# module_board.net
KiCad netlist of a schematic drawn in Altium Designer
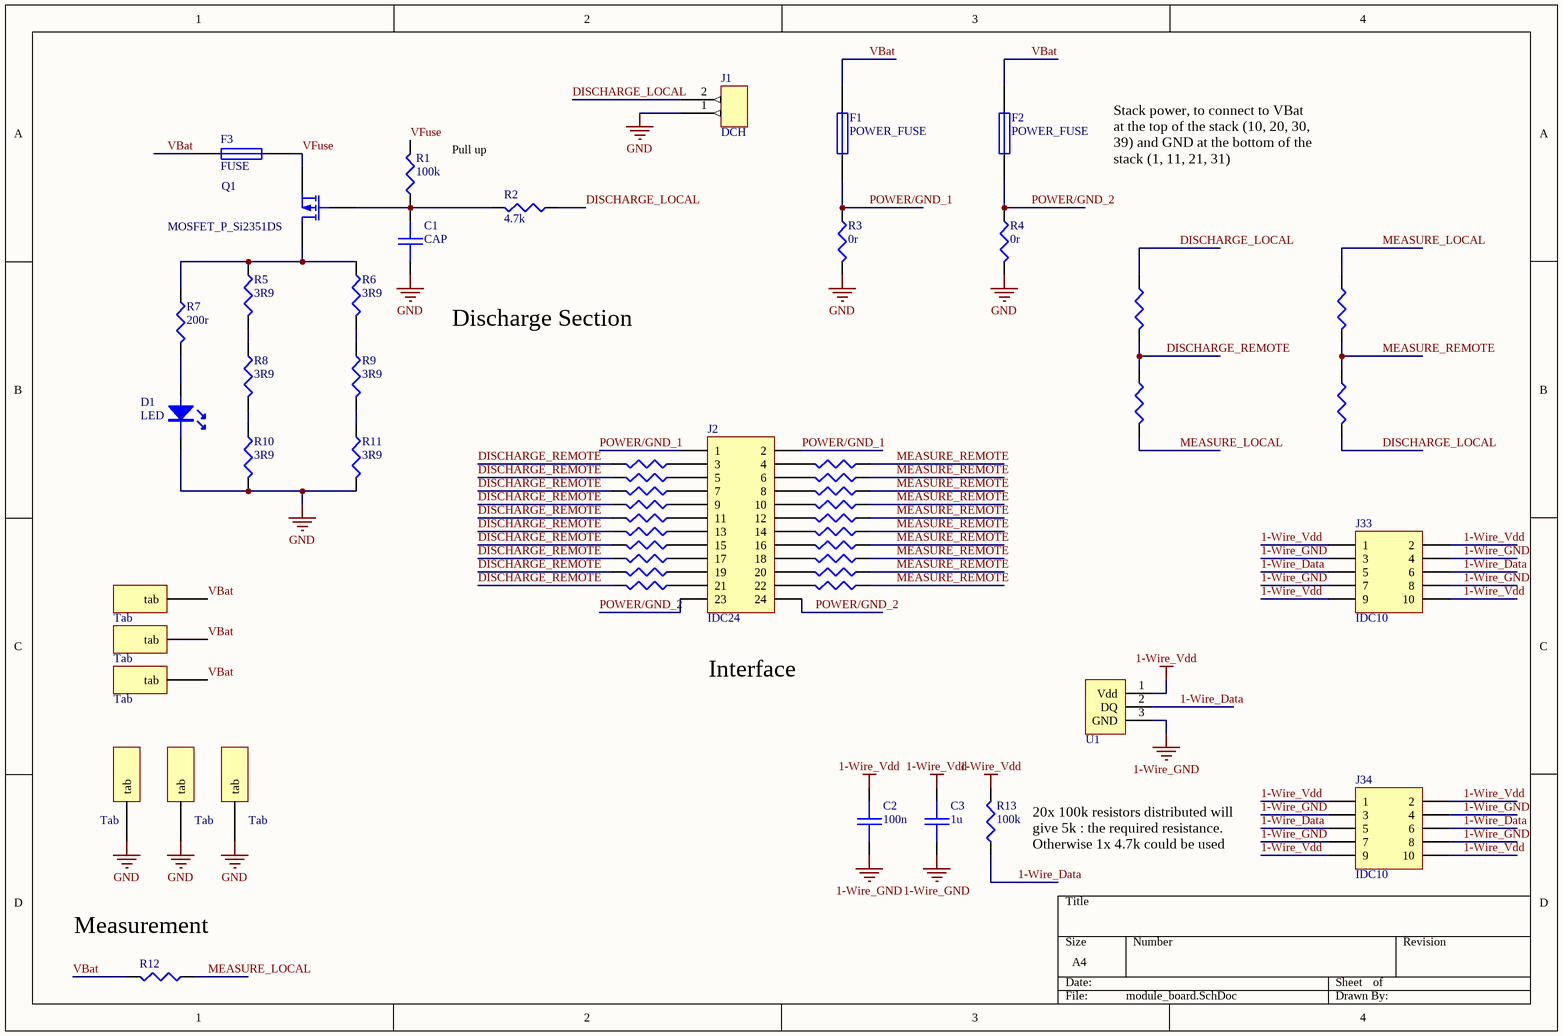
[diagram p0: module_board.SchDoc]

(export (version "E")
  (design (tool "Eeschema 10.0.6"))
  (components
    (comp (ref "C1")
      (value "CAP")
      (footprint "0603")
      (description "Capacitor")
      (libsource (lib "RCLDQ") (part "CAP"))
    )
    (comp (ref "C2")
      (value "100n")
      (footprint "0603")
      (description "Capacitor")
      (libsource (lib "RCLDQ") (part "CAP"))
    )
    (comp (ref "C3")
      (value "1u")
      (footprint "0805")
      (description "Capacitor")
      (libsource (lib "RCLDQ") (part "CAP"))
    )
    (comp (ref "D1") (value "LED") (footprint "0805LED") (libsource (lib "RCLDQ") (part "LED")))
    (comp (ref "F1")
      (value "POWER_FUSE")
      (footprint "LITTELFUSE-154")
      (description "Fuse")
      (libsource (lib "Miscellaneous") (part "FUSE"))
    )
    (comp (ref "F2")
      (value "POWER_FUSE")
      (footprint "LITTELFUSE-154")
      (description "Fuse")
      (libsource (lib "Miscellaneous") (part "FUSE"))
    )
    (comp (ref "F3")
      (value "FUSE")
      (footprint "LITTELFUSE-154")
      (description "Fuse")
      (libsource (lib "Miscellaneous") (part "FUSE"))
    )
    (comp (ref "J1") (value "DCH") (footprint "IDC2") (libsource (lib "Connectors") (part "CON2")))
    (comp (ref "J2")
      (value "IDC24")
      (footprint "IDC24")
      (description "Connector")
      (libsource (lib "Connectors") (part "IDC24"))
    )
    (comp (ref "J11") (value "Tab") (footprint "tab_connect") (libsource (lib "") (part "tab_connection_1")))
    (comp (ref "J20") (value "Tab") (footprint "tab_connect") (libsource (lib "") (part "tab_connection_1")))
    (comp (ref "J27") (value "Tab") (footprint "tab_connect") (libsource (lib "") (part "tab_connection_1")))
    (comp (ref "J30") (value "Tab") (footprint "tab_connect") (libsource (lib "BMS") (part "tab_connection")))
    (comp (ref "J31") (value "Tab") (footprint "tab_connect") (libsource (lib "BMS") (part "tab_connection")))
    (comp (ref "J32") (value "Tab") (footprint "tab_connect") (libsource (lib "BMS") (part "tab_connection")))
    (comp (ref "J33")
      (value "IDC10")
      (footprint "IDC10")
      (description "Connector")
      (libsource (lib "Connectors") (part "IDC10"))
    )
    (comp (ref "J34")
      (value "IDC10")
      (footprint "IDC10")
      (description "Connector")
      (libsource (lib "Connectors") (part "IDC10"))
    )
    (comp (ref "Q1")
      (value "MOSFET_P_Si2351DS")
      (footprint "SOT23-3")
      (description "Si2351DS P-Channel MOSFET")
      (fields (field (name "PUBLISHER") "Altium Limited"))
      (libsource (lib "RCLDQ") (part "MOSFET_P_Si2351DS"))
    )
    (comp (ref "R1")
      (value "100k")
      (footprint "0603")
      (description "Resistor")
      (libsource (lib "RCLDQ") (part "RES1"))
    )
    (comp (ref "R2")
      (value "4.7k")
      (footprint "1206")
      (description "Resistor")
      (libsource (lib "RCLDQ") (part "RES1"))
    )
    (comp (ref "R3")
      (value "~")
      (footprint "1206")
      (description "Resistor")
      (fields (field (name "RESISTANCE") "0r"))
      (libsource (lib "RCLDQ") (part "RES1"))
    )
    (comp (ref "R4")
      (value "~")
      (footprint "1206")
      (description "Resistor")
      (fields (field (name "RESISTANCE") "0r"))
      (libsource (lib "RCLDQ") (part "RES1"))
    )
    (comp (ref "R5")
      (value "3R9")
      (footprint "2512")
      (description "Resistor")
      (libsource (lib "RCLDQ") (part "RES1"))
    )
    (comp (ref "R6")
      (value "3R9")
      (footprint "2512")
      (description "Resistor")
      (libsource (lib "RCLDQ") (part "RES1"))
    )
    (comp (ref "R7")
      (value "200r")
      (footprint "0603")
      (description "Resistor")
      (libsource (lib "RCLDQ") (part "RES1"))
    )
    (comp (ref "R8")
      (value "3R9")
      (footprint "2512")
      (description "Resistor")
      (libsource (lib "RCLDQ") (part "RES1"))
    )
    (comp (ref "R9")
      (value "3R9")
      (footprint "2512")
      (description "Resistor")
      (libsource (lib "RCLDQ") (part "RES1"))
    )
    (comp (ref "R10")
      (value "3R9")
      (footprint "2512")
      (description "Resistor")
      (libsource (lib "RCLDQ") (part "RES1"))
    )
    (comp (ref "R11")
      (value "3R9")
      (footprint "2512")
      (description "Resistor")
      (libsource (lib "RCLDQ") (part "RES1"))
    )
    (comp (ref "R12")
      (value "4.7k")
      (footprint "1206")
      (description "Resistor")
      (libsource (lib "RCLDQ") (part "RES1"))
    )
    (comp (ref "R13")
      (value "100k")
      (footprint "0603")
      (description "Resistor")
      (libsource (lib "RCLDQ") (part "RES1"))
    )
    (comp (ref "R14")
      (value "0k")
      (footprint "0603")
      (description "Resistor")
      (libsource (lib "RCLDQ") (part "RES1"))
    )
    (comp (ref "R15")
      (value "0k")
      (footprint "0603")
      (description "Resistor")
      (libsource (lib "RCLDQ") (part "RES1"))
    )
    (comp (ref "R16")
      (value "0k")
      (footprint "0603")
      (description "Resistor")
      (libsource (lib "RCLDQ") (part "RES1"))
    )
    (comp (ref "R17")
      (value "0k")
      (footprint "0603")
      (description "Resistor")
      (libsource (lib "RCLDQ") (part "RES1"))
    )
    (comp (ref "R18")
      (value "0k")
      (footprint "0603")
      (description "Resistor")
      (libsource (lib "RCLDQ") (part "RES1"))
    )
    (comp (ref "R19")
      (value "0k")
      (footprint "0603")
      (description "Resistor")
      (libsource (lib "RCLDQ") (part "RES1"))
    )
    (comp (ref "R20")
      (value "0k")
      (footprint "0603")
      (description "Resistor")
      (libsource (lib "RCLDQ") (part "RES1"))
    )
    (comp (ref "R21")
      (value "0k")
      (footprint "0603")
      (description "Resistor")
      (libsource (lib "RCLDQ") (part "RES1"))
    )
    (comp (ref "R22")
      (value "0k")
      (footprint "0603")
      (description "Resistor")
      (libsource (lib "RCLDQ") (part "RES1"))
    )
    (comp (ref "R23")
      (value "0k")
      (footprint "0603")
      (description "Resistor")
      (libsource (lib "RCLDQ") (part "RES1"))
    )
    (comp (ref "R24")
      (value "0k")
      (footprint "0603")
      (description "Resistor")
      (libsource (lib "RCLDQ") (part "RES1"))
    )
    (comp (ref "R25")
      (value "0k")
      (footprint "0603")
      (description "Resistor")
      (libsource (lib "RCLDQ") (part "RES1"))
    )
    (comp (ref "R26")
      (value "0k")
      (footprint "0603")
      (description "Resistor")
      (libsource (lib "RCLDQ") (part "RES1"))
    )
    (comp (ref "R27")
      (value "0k")
      (footprint "0603")
      (description "Resistor")
      (libsource (lib "RCLDQ") (part "RES1"))
    )
    (comp (ref "R28")
      (value "0k")
      (footprint "0603")
      (description "Resistor")
      (libsource (lib "RCLDQ") (part "RES1"))
    )
    (comp (ref "R29")
      (value "0k")
      (footprint "0603")
      (description "Resistor")
      (libsource (lib "RCLDQ") (part "RES1"))
    )
    (comp (ref "R30")
      (value "0k")
      (footprint "0603")
      (description "Resistor")
      (libsource (lib "RCLDQ") (part "RES1"))
    )
    (comp (ref "R31")
      (value "0k")
      (footprint "0603")
      (description "Resistor")
      (libsource (lib "RCLDQ") (part "RES1"))
    )
    (comp (ref "R32")
      (value "0k")
      (footprint "0603")
      (description "Resistor")
      (libsource (lib "RCLDQ") (part "RES1"))
    )
    (comp (ref "R33")
      (value "0k")
      (footprint "0603")
      (description "Resistor")
      (libsource (lib "RCLDQ") (part "RES1"))
    )
    (comp (ref "R34")
      (value "0k")
      (footprint "0603")
      (description "Resistor")
      (libsource (lib "RCLDQ") (part "RES1"))
    )
    (comp (ref "R35")
      (value "0k")
      (footprint "0603")
      (description "Resistor")
      (libsource (lib "RCLDQ") (part "RES1"))
    )
    (comp (ref "R36")
      (value "0k")
      (footprint "0603")
      (description "Resistor")
      (libsource (lib "RCLDQ") (part "RES1"))
    )
    (comp (ref "R37")
      (value "0k")
      (footprint "0603")
      (description "Resistor")
      (libsource (lib "RCLDQ") (part "RES1"))
    )
    (comp (ref "U1")
      (value "DS18B20")
      (footprint "TO-92")
      (description "DS18B20 1-Wire Temperature sensor")
      (libsource (lib "BMS") (part "DS18B20"))
    )
  )
  (nets
    (net (code "1") (name "/1-Wire_Data") (class "Default")
      (node (ref "J33") (pin "5") (pinfunction "5_5") (pintype "passive"))
      (node (ref "J33") (pin "6") (pinfunction "6_6") (pintype "passive"))
      (node (ref "J34") (pin "5") (pinfunction "5_5") (pintype "passive"))
      (node (ref "J34") (pin "6") (pinfunction "6_6") (pintype "passive"))
      (node (ref "R13") (pin "1") (pinfunction "1_1") (pintype "passive"))
      (node (ref "U1") (pin "2") (pinfunction "DQ_2") (pintype "passive"))
    )
    (net (code "2") (name "/DISCHARGE_LOCAL") (class "Default")
      (node (ref "J1") (pin "2") (pinfunction "2_2") (pintype "output"))
      (node (ref "R2") (pin "1") (pinfunction "1_1") (pintype "passive"))
      (node (ref "R34") (pin "1") (pinfunction "1_1") (pintype "passive"))
      (node (ref "R37") (pin "2") (pinfunction "2_2") (pintype "passive"))
    )
    (net (code "3") (name "/DISCHARGE_REMOTE") (class "Default")
      (node (ref "R14") (pin "2") (pinfunction "2_2") (pintype "passive"))
      (node (ref "R16") (pin "2") (pinfunction "2_2") (pintype "passive"))
      (node (ref "R18") (pin "2") (pinfunction "2_2") (pintype "passive"))
      (node (ref "R20") (pin "2") (pinfunction "2_2") (pintype "passive"))
      (node (ref "R22") (pin "2") (pinfunction "2_2") (pintype "passive"))
      (node (ref "R24") (pin "2") (pinfunction "2_2") (pintype "passive"))
      (node (ref "R26") (pin "2") (pinfunction "2_2") (pintype "passive"))
      (node (ref "R28") (pin "2") (pinfunction "2_2") (pintype "passive"))
      (node (ref "R30") (pin "2") (pinfunction "2_2") (pintype "passive"))
      (node (ref "R32") (pin "2") (pinfunction "2_2") (pintype "passive"))
      (node (ref "R34") (pin "2") (pinfunction "2_2") (pintype "passive"))
      (node (ref "R36") (pin "1") (pinfunction "1_1") (pintype "passive"))
    )
    (net (code "4") (name "/MEASURE_LOCAL") (class "Default")
      (node (ref "R12") (pin "1") (pinfunction "1_1") (pintype "passive"))
      (node (ref "R35") (pin "1") (pinfunction "1_1") (pintype "passive"))
      (node (ref "R36") (pin "2") (pinfunction "2_2") (pintype "passive"))
    )
    (net (code "5") (name "/MEASURE_REMOTE") (class "Default")
      (node (ref "R15") (pin "1") (pinfunction "1_1") (pintype "passive"))
      (node (ref "R17") (pin "1") (pinfunction "1_1") (pintype "passive"))
      (node (ref "R19") (pin "1") (pinfunction "1_1") (pintype "passive"))
      (node (ref "R21") (pin "1") (pinfunction "1_1") (pintype "passive"))
      (node (ref "R23") (pin "1") (pinfunction "1_1") (pintype "passive"))
      (node (ref "R25") (pin "1") (pinfunction "1_1") (pintype "passive"))
      (node (ref "R27") (pin "1") (pinfunction "1_1") (pintype "passive"))
      (node (ref "R29") (pin "1") (pinfunction "1_1") (pintype "passive"))
      (node (ref "R31") (pin "1") (pinfunction "1_1") (pintype "passive"))
      (node (ref "R33") (pin "1") (pinfunction "1_1") (pintype "passive"))
      (node (ref "R35") (pin "2") (pinfunction "2_2") (pintype "passive"))
      (node (ref "R37") (pin "1") (pinfunction "1_1") (pintype "passive"))
    )
    (net (code "6") (name "/POWER{slash}GND_1") (class "Default")
      (node (ref "F1") (pin "1") (pinfunction "1_1") (pintype "passive"))
      (node (ref "J2") (pin "1") (pinfunction "1_1") (pintype "passive"))
      (node (ref "J2") (pin "2") (pinfunction "2_2") (pintype "passive"))
      (node (ref "R3") (pin "1") (pinfunction "1_1") (pintype "passive"))
    )
    (net (code "7") (name "/POWER{slash}GND_2") (class "Default")
      (node (ref "F2") (pin "1") (pinfunction "1_1") (pintype "passive"))
      (node (ref "J2") (pin "23") (pinfunction "23_23") (pintype "passive"))
      (node (ref "J2") (pin "24") (pinfunction "24_24") (pintype "passive"))
      (node (ref "R4") (pin "1") (pinfunction "1_1") (pintype "passive"))
    )
    (net (code "8") (name "/VBat") (class "Default")
      (node (ref "F1") (pin "2") (pinfunction "2_2") (pintype "passive"))
      (node (ref "F2") (pin "2") (pinfunction "2_2") (pintype "passive"))
      (node (ref "F3") (pin "1") (pinfunction "1_1") (pintype "passive"))
      (node (ref "J11") (pin "0") (pinfunction "tab_0") (pintype "passive"))
      (node (ref "J20") (pin "0") (pinfunction "tab_0") (pintype "passive"))
      (node (ref "J27") (pin "0") (pinfunction "tab_0") (pintype "passive"))
      (node (ref "R12") (pin "2") (pinfunction "2_2") (pintype "passive"))
    )
    (net (code "9") (name "/VFuse") (class "Default")
      (node (ref "F3") (pin "2") (pinfunction "2_2") (pintype "passive"))
      (node (ref "Q1") (pin "2") (pinfunction "S_2") (pintype "passive"))
      (node (ref "R1") (pin "2") (pinfunction "2_2") (pintype "passive"))
    )
    (net (code "10") (name "1-Wire_GND") (class "Default")
      (node (ref "C2") (pin "2") (pinfunction "2_2") (pintype "passive"))
      (node (ref "C3") (pin "2") (pinfunction "2_2") (pintype "passive"))
      (node (ref "J33") (pin "3") (pinfunction "3_3") (pintype "passive"))
      (node (ref "J33") (pin "4") (pinfunction "4_4") (pintype "passive"))
      (node (ref "J33") (pin "7") (pinfunction "7_7") (pintype "passive"))
      (node (ref "J33") (pin "8") (pinfunction "8_8") (pintype "passive"))
      (node (ref "J34") (pin "3") (pinfunction "3_3") (pintype "passive"))
      (node (ref "J34") (pin "4") (pinfunction "4_4") (pintype "passive"))
      (node (ref "J34") (pin "7") (pinfunction "7_7") (pintype "passive"))
      (node (ref "J34") (pin "8") (pinfunction "8_8") (pintype "passive"))
      (node (ref "U1") (pin "3") (pinfunction "GND_3") (pintype "passive"))
    )
    (net (code "11") (name "1-Wire_Vdd") (class "Default")
      (node (ref "C2") (pin "1") (pinfunction "1_1") (pintype "passive"))
      (node (ref "C3") (pin "1") (pinfunction "1_1") (pintype "passive"))
      (node (ref "J33") (pin "1") (pinfunction "1_1") (pintype "passive"))
      (node (ref "J33") (pin "10") (pinfunction "10_10") (pintype "passive"))
      (node (ref "J33") (pin "2") (pinfunction "2_2") (pintype "passive"))
      (node (ref "J33") (pin "9") (pinfunction "9_9") (pintype "passive"))
      (node (ref "J34") (pin "1") (pinfunction "1_1") (pintype "passive"))
      (node (ref "J34") (pin "10") (pinfunction "10_10") (pintype "passive"))
      (node (ref "J34") (pin "2") (pinfunction "2_2") (pintype "passive"))
      (node (ref "J34") (pin "9") (pinfunction "9_9") (pintype "passive"))
      (node (ref "R13") (pin "2") (pinfunction "2_2") (pintype "passive"))
      (node (ref "U1") (pin "1") (pinfunction "Vdd_1") (pintype "passive"))
    )
    (net (code "12") (name "GND") (class "Default")
      (node (ref "C1") (pin "2") (pinfunction "2_2") (pintype "passive"))
      (node (ref "D1") (pin "K") (pinfunction "K_K") (pintype "passive"))
      (node (ref "J1") (pin "1") (pinfunction "1_1") (pintype "output"))
      (node (ref "J30") (pin "0") (pinfunction "tab_0") (pintype "passive"))
      (node (ref "J31") (pin "0") (pinfunction "tab_0") (pintype "passive"))
      (node (ref "J32") (pin "0") (pinfunction "tab_0") (pintype "passive"))
      (node (ref "R10") (pin "2") (pinfunction "2_2") (pintype "passive"))
      (node (ref "R11") (pin "2") (pinfunction "2_2") (pintype "passive"))
      (node (ref "R3") (pin "2") (pinfunction "2_2") (pintype "passive"))
      (node (ref "R4") (pin "2") (pinfunction "2_2") (pintype "passive"))
    )
    (net (code "13") (name "Net-(D1-PadA)") (class "Default")
      (node (ref "D1") (pin "A") (pinfunction "A_A") (pintype "passive"))
      (node (ref "R7") (pin "2") (pinfunction "2_2") (pintype "passive"))
    )
    (net (code "14") (name "Net-(J2-Pad3)") (class "Default")
      (node (ref "J2") (pin "3") (pinfunction "3_3") (pintype "passive"))
      (node (ref "R14") (pin "1") (pinfunction "1_1") (pintype "passive"))
    )
    (net (code "15") (name "Net-(J2-Pad4)") (class "Default")
      (node (ref "J2") (pin "4") (pinfunction "4_4") (pintype "passive"))
      (node (ref "R15") (pin "2") (pinfunction "2_2") (pintype "passive"))
    )
    (net (code "16") (name "Net-(J2-Pad5)") (class "Default")
      (node (ref "J2") (pin "5") (pinfunction "5_5") (pintype "passive"))
      (node (ref "R16") (pin "1") (pinfunction "1_1") (pintype "passive"))
    )
    (net (code "17") (name "Net-(J2-Pad6)") (class "Default")
      (node (ref "J2") (pin "6") (pinfunction "6_6") (pintype "passive"))
      (node (ref "R17") (pin "2") (pinfunction "2_2") (pintype "passive"))
    )
    (net (code "18") (name "Net-(J2-Pad7)") (class "Default")
      (node (ref "J2") (pin "7") (pinfunction "7_7") (pintype "passive"))
      (node (ref "R18") (pin "1") (pinfunction "1_1") (pintype "passive"))
    )
    (net (code "19") (name "Net-(J2-Pad8)") (class "Default")
      (node (ref "J2") (pin "8") (pinfunction "8_8") (pintype "passive"))
      (node (ref "R19") (pin "2") (pinfunction "2_2") (pintype "passive"))
    )
    (net (code "20") (name "Net-(J2-Pad9)") (class "Default")
      (node (ref "J2") (pin "9") (pinfunction "9_9") (pintype "passive"))
      (node (ref "R20") (pin "1") (pinfunction "1_1") (pintype "passive"))
    )
    (net (code "21") (name "Net-(J2-Pad10)") (class "Default")
      (node (ref "J2") (pin "10") (pinfunction "10_10") (pintype "passive"))
      (node (ref "R21") (pin "2") (pinfunction "2_2") (pintype "passive"))
    )
    (net (code "22") (name "Net-(J2-Pad11)") (class "Default")
      (node (ref "J2") (pin "11") (pinfunction "11_11") (pintype "passive"))
      (node (ref "R22") (pin "1") (pinfunction "1_1") (pintype "passive"))
    )
    (net (code "23") (name "Net-(J2-Pad12)") (class "Default")
      (node (ref "J2") (pin "12") (pinfunction "12_12") (pintype "passive"))
      (node (ref "R23") (pin "2") (pinfunction "2_2") (pintype "passive"))
    )
    (net (code "24") (name "Net-(J2-Pad13)") (class "Default")
      (node (ref "J2") (pin "13") (pinfunction "13_13") (pintype "passive"))
      (node (ref "R24") (pin "1") (pinfunction "1_1") (pintype "passive"))
    )
    (net (code "25") (name "Net-(J2-Pad14)") (class "Default")
      (node (ref "J2") (pin "14") (pinfunction "14_14") (pintype "passive"))
      (node (ref "R25") (pin "2") (pinfunction "2_2") (pintype "passive"))
    )
    (net (code "26") (name "Net-(J2-Pad15)") (class "Default")
      (node (ref "J2") (pin "15") (pinfunction "15_15") (pintype "passive"))
      (node (ref "R26") (pin "1") (pinfunction "1_1") (pintype "passive"))
    )
    (net (code "27") (name "Net-(J2-Pad16)") (class "Default")
      (node (ref "J2") (pin "16") (pinfunction "16_16") (pintype "passive"))
      (node (ref "R27") (pin "2") (pinfunction "2_2") (pintype "passive"))
    )
    (net (code "28") (name "Net-(J2-Pad17)") (class "Default")
      (node (ref "J2") (pin "17") (pinfunction "17_17") (pintype "passive"))
      (node (ref "R28") (pin "1") (pinfunction "1_1") (pintype "passive"))
    )
    (net (code "29") (name "Net-(J2-Pad18)") (class "Default")
      (node (ref "J2") (pin "18") (pinfunction "18_18") (pintype "passive"))
      (node (ref "R29") (pin "2") (pinfunction "2_2") (pintype "passive"))
    )
    (net (code "30") (name "Net-(J2-Pad19)") (class "Default")
      (node (ref "J2") (pin "19") (pinfunction "19_19") (pintype "passive"))
      (node (ref "R30") (pin "1") (pinfunction "1_1") (pintype "passive"))
    )
    (net (code "31") (name "Net-(J2-Pad20)") (class "Default")
      (node (ref "J2") (pin "20") (pinfunction "20_20") (pintype "passive"))
      (node (ref "R31") (pin "2") (pinfunction "2_2") (pintype "passive"))
    )
    (net (code "32") (name "Net-(J2-Pad21)") (class "Default")
      (node (ref "J2") (pin "21") (pinfunction "21_21") (pintype "passive"))
      (node (ref "R32") (pin "1") (pinfunction "1_1") (pintype "passive"))
    )
    (net (code "33") (name "Net-(J2-Pad22)") (class "Default")
      (node (ref "J2") (pin "22") (pinfunction "22_22") (pintype "passive"))
      (node (ref "R33") (pin "2") (pinfunction "2_2") (pintype "passive"))
    )
    (net (code "34") (name "Net-(Q1-D)") (class "Default")
      (node (ref "Q1") (pin "3") (pinfunction "D_3") (pintype "passive"))
      (node (ref "R5") (pin "1") (pinfunction "1_1") (pintype "passive"))
      (node (ref "R6") (pin "1") (pinfunction "1_1") (pintype "passive"))
      (node (ref "R7") (pin "1") (pinfunction "1_1") (pintype "passive"))
    )
    (net (code "35") (name "Net-(Q1-G)") (class "Default")
      (node (ref "C1") (pin "1") (pinfunction "1_1") (pintype "passive"))
      (node (ref "Q1") (pin "1") (pinfunction "G_1") (pintype "passive"))
      (node (ref "R1") (pin "1") (pinfunction "1_1") (pintype "passive"))
      (node (ref "R2") (pin "2") (pinfunction "2_2") (pintype "passive"))
    )
    (net (code "36") (name "Net-(R5-Pad2)") (class "Default")
      (node (ref "R5") (pin "2") (pinfunction "2_2") (pintype "passive"))
      (node (ref "R8") (pin "1") (pinfunction "1_1") (pintype "passive"))
    )
    (net (code "37") (name "Net-(R6-Pad2)") (class "Default")
      (node (ref "R6") (pin "2") (pinfunction "2_2") (pintype "passive"))
      (node (ref "R9") (pin "1") (pinfunction "1_1") (pintype "passive"))
    )
    (net (code "38") (name "Net-(R10-Pad1)") (class "Default")
      (node (ref "R10") (pin "1") (pinfunction "1_1") (pintype "passive"))
      (node (ref "R8") (pin "2") (pinfunction "2_2") (pintype "passive"))
    )
    (net (code "39") (name "Net-(R11-Pad1)") (class "Default")
      (node (ref "R11") (pin "1") (pinfunction "1_1") (pintype "passive"))
      (node (ref "R9") (pin "2") (pinfunction "2_2") (pintype "passive"))
    )
  )
)
